# actik-retrofit-r1.net
KiCad netlist of a schematic drawn in EAGLE
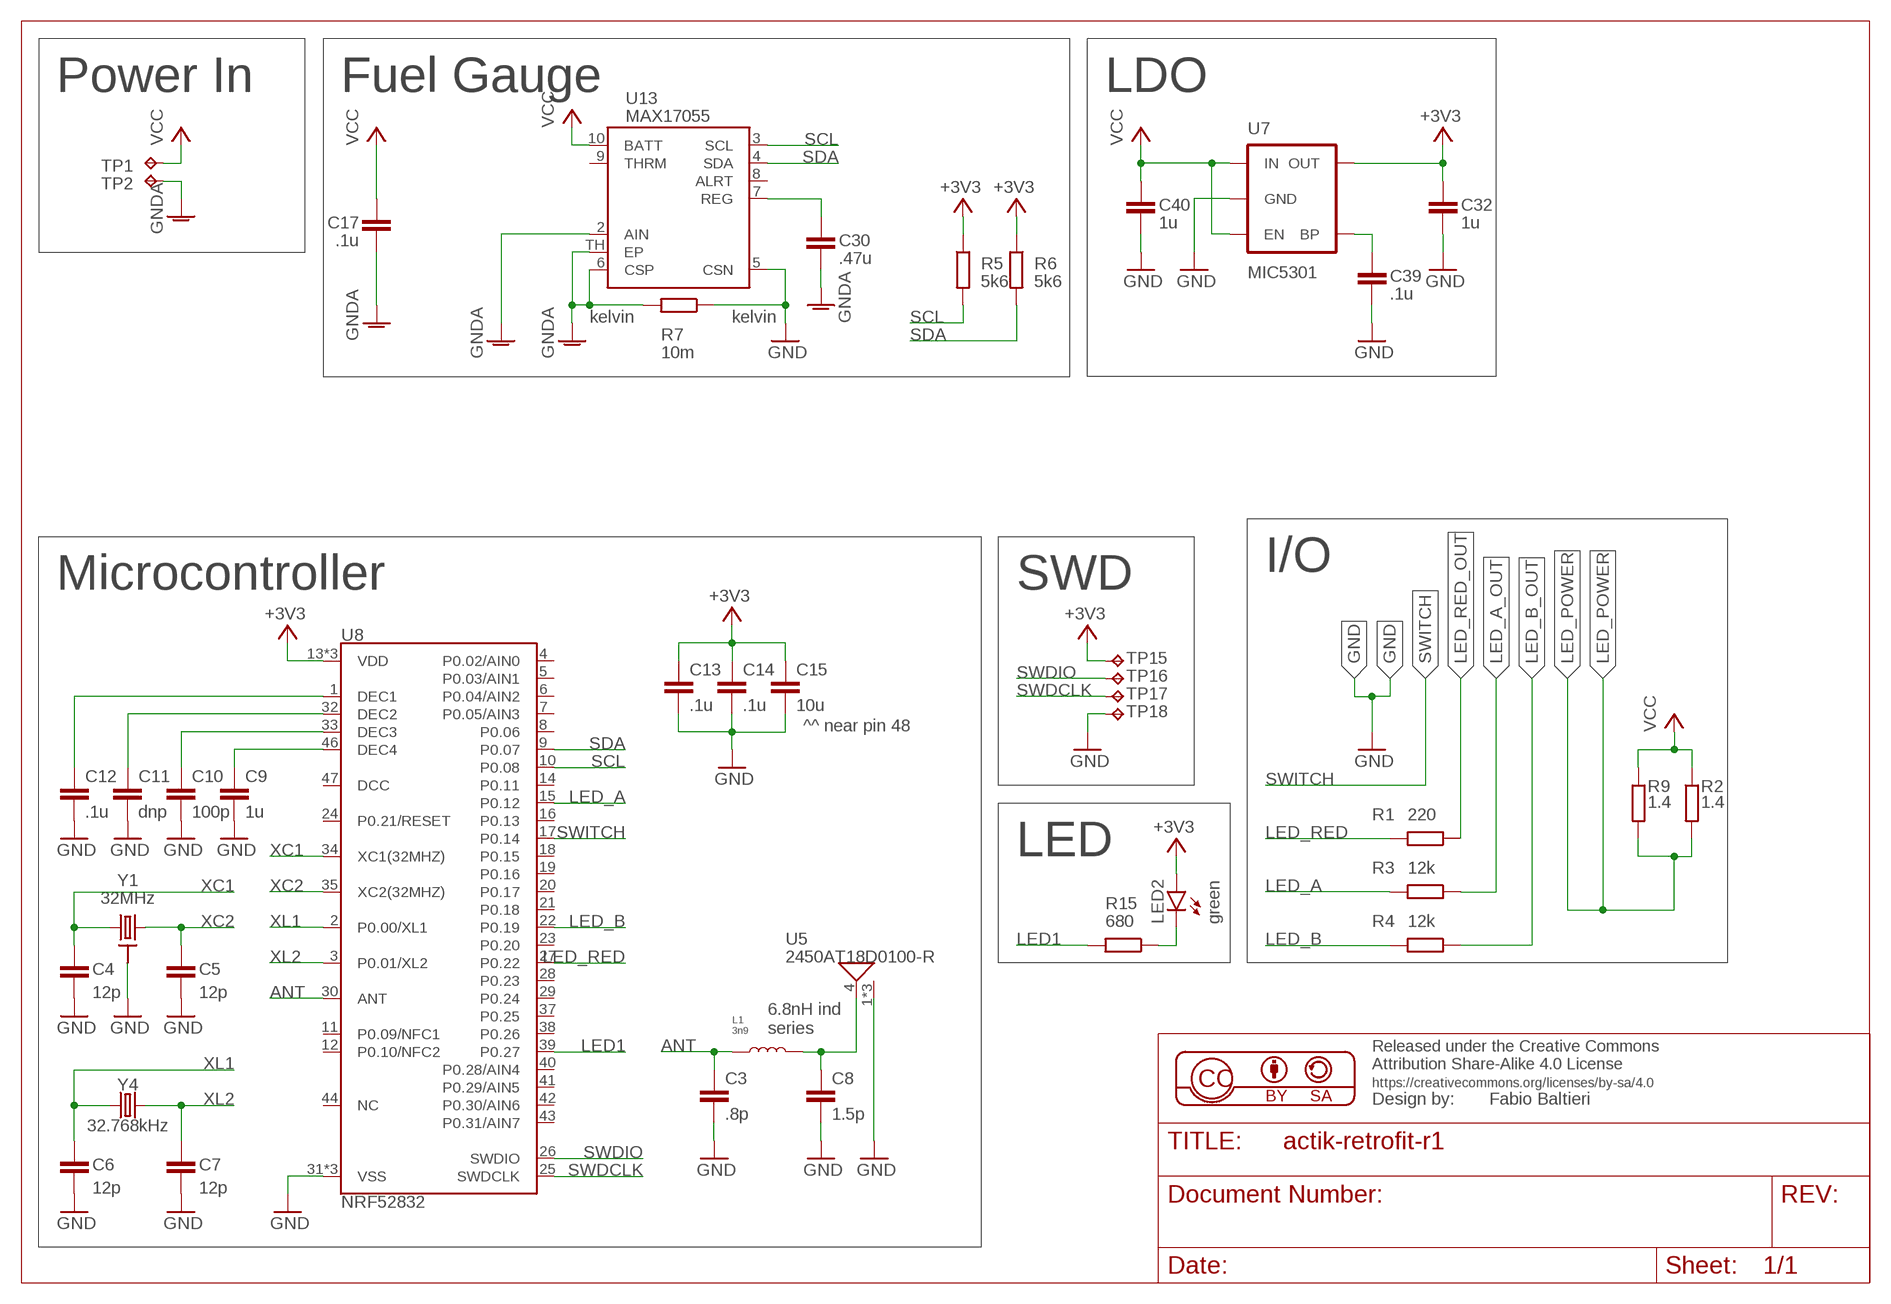
[diagram p0: schematic, sheet 1]

(export (version "E")
  (design (tool "Eeschema 10.0.6"))
  (components
    (comp (ref "C3")
      (value ".8p")
      (footprint "eagle-import:0603")
      (libsource (lib "eagle-import") (part "C0603"))
    )
    (comp (ref "C4")
      (value "12p")
      (footprint "eagle-import:0603")
      (libsource (lib "eagle-import") (part "C0603"))
    )
    (comp (ref "C5")
      (value "12p")
      (footprint "eagle-import:0603")
      (libsource (lib "eagle-import") (part "C0603"))
    )
    (comp (ref "C6")
      (value "12p")
      (footprint "eagle-import:0603")
      (libsource (lib "eagle-import") (part "C0603"))
    )
    (comp (ref "C7")
      (value "12p")
      (footprint "eagle-import:0603")
      (libsource (lib "eagle-import") (part "C0603"))
    )
    (comp (ref "C8")
      (value "1.5p")
      (footprint "eagle-import:0603")
      (libsource (lib "eagle-import") (part "C0603"))
    )
    (comp (ref "C9")
      (value "1u")
      (footprint "eagle-import:0603")
      (libsource (lib "eagle-import") (part "C0603"))
    )
    (comp (ref "C10")
      (value "100p")
      (footprint "eagle-import:0603")
      (libsource (lib "eagle-import") (part "C0603"))
    )
    (comp (ref "C11")
      (value "dnp")
      (footprint "eagle-import:0603")
      (libsource (lib "eagle-import") (part "C0603"))
    )
    (comp (ref "C12")
      (value ".1u")
      (footprint "eagle-import:0603")
      (libsource (lib "eagle-import") (part "C0603"))
    )
    (comp (ref "C13")
      (value ".1u")
      (footprint "eagle-import:0603")
      (libsource (lib "eagle-import") (part "C0603"))
    )
    (comp (ref "C14")
      (value ".1u")
      (footprint "eagle-import:0603")
      (libsource (lib "eagle-import") (part "C0603"))
    )
    (comp (ref "C15")
      (value "10u")
      (footprint "eagle-import:0603")
      (libsource (lib "eagle-import") (part "C0603"))
    )
    (comp (ref "C17")
      (value ".1u")
      (footprint "eagle-import:0603")
      (libsource (lib "eagle-import") (part "C0603"))
    )
    (comp (ref "C30")
      (value ".47u")
      (footprint "eagle-import:0603")
      (libsource (lib "eagle-import") (part "C0603"))
    )
    (comp (ref "C32")
      (value "1u")
      (footprint "eagle-import:0603")
      (libsource (lib "eagle-import") (part "C0603"))
    )
    (comp (ref "C39")
      (value ".1u")
      (footprint "eagle-import:0603")
      (libsource (lib "eagle-import") (part "C0603"))
    )
    (comp (ref "C40")
      (value "1u")
      (footprint "eagle-import:0603")
      (libsource (lib "eagle-import") (part "C0603"))
    )
    (comp (ref "L1")
      (value "3n9")
      (footprint "eagle-import:L0603")
      (libsource (lib "eagle-import") (part "INDUCTOR_0603"))
    )
    (comp (ref "LED2")
      (value "green")
      (footprint "eagle-import:SML0805")
      (libsource (lib "eagle-import") (part "LEDSML0805"))
    )
    (comp (ref "R1")
      (value "220")
      (footprint "eagle-import:0603")
      (libsource (lib "eagle-import") (part "R0603"))
    )
    (comp (ref "R2")
      (value "1.4")
      (footprint "eagle-import:R3225")
      (libsource (lib "eagle-import") (part "R-EU_R3225"))
    )
    (comp (ref "R3")
      (value "12k")
      (footprint "eagle-import:0603")
      (libsource (lib "eagle-import") (part "R0603"))
    )
    (comp (ref "R4")
      (value "12k")
      (footprint "eagle-import:0603")
      (libsource (lib "eagle-import") (part "R0603"))
    )
    (comp (ref "R5")
      (value "5k6")
      (footprint "eagle-import:0603")
      (libsource (lib "eagle-import") (part "R0603"))
    )
    (comp (ref "R6")
      (value "5k6")
      (footprint "eagle-import:0603")
      (libsource (lib "eagle-import") (part "R0603"))
    )
    (comp (ref "R7")
      (value "10m")
      (footprint "eagle-import:0603")
      (libsource (lib "eagle-import") (part "R0603"))
    )
    (comp (ref "R9")
      (value "1.4")
      (footprint "eagle-import:R3225")
      (libsource (lib "eagle-import") (part "R-EU_R3225"))
    )
    (comp (ref "R15")
      (value "680")
      (footprint "eagle-import:0603")
      (libsource (lib "eagle-import") (part "R0603"))
    )
    (comp (ref "TP1")
      (value "TPPAD1-13")
      (footprint "eagle-import:P1-13")
      (libsource (lib "eagle-import") (part "TPPAD1-13"))
    )
    (comp (ref "TP2")
      (value "TPPAD1-13")
      (footprint "eagle-import:P1-13")
      (libsource (lib "eagle-import") (part "TPPAD1-13"))
    )
    (comp (ref "TP15")
      (value "TPTP10R")
      (footprint "eagle-import:TP10R")
      (libsource (lib "eagle-import") (part "TPTP10R"))
    )
    (comp (ref "TP16")
      (value "TPTP10R")
      (footprint "eagle-import:TP10R")
      (libsource (lib "eagle-import") (part "TPTP10R"))
    )
    (comp (ref "TP17")
      (value "TPTP10R")
      (footprint "eagle-import:TP10R")
      (libsource (lib "eagle-import") (part "TPTP10R"))
    )
    (comp (ref "TP18")
      (value "TPTP10R")
      (footprint "eagle-import:TP10R")
      (libsource (lib "eagle-import") (part "TPTP10R"))
    )
    (comp (ref "U5")
      (value "2450AT18D0100-R")
      (footprint "eagle-import:2450AT18D0100-R")
      (libsource (lib "eagle-import") (part "2450AT18D0100-R"))
    )
    (comp (ref "U7")
      (value "MIC5301")
      (footprint "eagle-import:SOT23-5")
      (libsource (lib "eagle-import") (part "V_REG_LDOSMD"))
    )
    (comp (ref "U8")
      (value "NRF52832")
      (footprint "eagle-import:QFN48-6X6MM")
      (libsource (lib "eagle-import") (part "NRF52832"))
    )
    (comp (ref "U13")
      (value "MAX17055")
      (footprint "eagle-import:TDFN10-2X2.5")
      (libsource (lib "eagle-import") (part "MAX17055"))
    )
    (comp (ref "Y1")
      (value "32MHz")
      (footprint "eagle-import:XTAL-2X1.6")
      (libsource (lib "eagle-import") (part "XTAL-GND-2X1.6"))
    )
    (comp (ref "Y4")
      (value "32.768kHz")
      (footprint "eagle-import:CRYSTAL-SMD-3.2X1.5MM")
      (libsource (lib "eagle-import") (part "CRYSTAL-32.768KHZSMD-3.2X1.5"))
    )
  )
  (nets
    (net (code "1") (name "+3V3") (class "Default")
      (node (ref "C13") (pin "1") (pinfunction "1_1") (pintype "passive"))
      (node (ref "C14") (pin "1") (pinfunction "1_1") (pintype "passive"))
      (node (ref "C15") (pin "1") (pinfunction "1_1") (pintype "passive"))
      (node (ref "C32") (pin "1") (pinfunction "1_1") (pintype "passive"))
      (node (ref "LED2") (pin "A") (pinfunction "A_A") (pintype "passive"))
      (node (ref "R5") (pin "1") (pinfunction "1_1") (pintype "passive"))
      (node (ref "R6") (pin "1") (pinfunction "1_1") (pintype "passive"))
      (node (ref "TP15") (pin "TP") (pinfunction "TP_TP") (pintype "input"))
      (node (ref "U7") (pin "5") (pinfunction "OUT_5") (pintype "passive"))
      (node (ref "U8") (pin "13") (pinfunction "VDD_13") (pintype "bidirectional"))
      (node (ref "U8") (pin "36") (pinfunction "VDD_36") (pintype "bidirectional"))
      (node (ref "U8") (pin "48") (pinfunction "VDD_48") (pintype "bidirectional"))
    )
    (net (code "2") (name "/ANT") (class "Default")
      (node (ref "C3") (pin "1") (pinfunction "1_1") (pintype "passive"))
      (node (ref "L1") (pin "P$1") (pinfunction "P$1_P$1") (pintype "passive"))
      (node (ref "U8") (pin "30") (pinfunction "ANT_30") (pintype "bidirectional"))
    )
    (net (code "3") (name "/LED1") (class "Default")
      (node (ref "R15") (pin "2") (pinfunction "2_2") (pintype "passive"))
      (node (ref "U8") (pin "39") (pinfunction "P0.27_39") (pintype "bidirectional"))
    )
    (net (code "4") (name "/LED_A") (class "Default")
      (node (ref "R3") (pin "2") (pinfunction "2_2") (pintype "passive"))
      (node (ref "U8") (pin "15") (pinfunction "P0.12_15") (pintype "bidirectional"))
    )
    (net (code "5") (name "/LED_B") (class "Default")
      (node (ref "R4") (pin "2") (pinfunction "2_2") (pintype "passive"))
      (node (ref "U8") (pin "22") (pinfunction "P0.19_22") (pintype "bidirectional"))
    )
    (net (code "6") (name "/LED_RED") (class "Default")
      (node (ref "R1") (pin "2") (pinfunction "2_2") (pintype "passive"))
      (node (ref "U8") (pin "27") (pinfunction "P0.22_27") (pintype "bidirectional"))
    )
    (net (code "7") (name "/SCL") (class "Default")
      (node (ref "R5") (pin "2") (pinfunction "2_2") (pintype "passive"))
      (node (ref "U13") (pin "3") (pinfunction "SCL_3") (pintype "bidirectional"))
      (node (ref "U8") (pin "10") (pinfunction "P0.08_10") (pintype "bidirectional"))
    )
    (net (code "8") (name "/SDA") (class "Default")
      (node (ref "R6") (pin "2") (pinfunction "2_2") (pintype "passive"))
      (node (ref "U13") (pin "4") (pinfunction "SDA_4") (pintype "bidirectional"))
      (node (ref "U8") (pin "9") (pinfunction "P0.07_9") (pintype "bidirectional"))
    )
    (net (code "9") (name "/SWDCLK") (class "Default")
      (node (ref "TP17") (pin "TP") (pinfunction "TP_TP") (pintype "input"))
      (node (ref "U8") (pin "25") (pinfunction "SWDCLK_25") (pintype "bidirectional"))
    )
    (net (code "10") (name "/SWDIO") (class "Default")
      (node (ref "TP16") (pin "TP") (pinfunction "TP_TP") (pintype "input"))
      (node (ref "U8") (pin "26") (pinfunction "SWDIO_26") (pintype "bidirectional"))
    )
    (net (code "11") (name "/XC1") (class "Default")
      (node (ref "C4") (pin "1") (pinfunction "1_1") (pintype "passive"))
      (node (ref "U8") (pin "34") (pinfunction "XC1(32MHZ)_34") (pintype "bidirectional"))
      (node (ref "Y1") (pin "1") (pinfunction "1_1") (pintype "passive"))
    )
    (net (code "12") (name "/XC2") (class "Default")
      (node (ref "C5") (pin "1") (pinfunction "1_1") (pintype "passive"))
      (node (ref "U8") (pin "35") (pinfunction "XC2(32MHZ)_35") (pintype "bidirectional"))
      (node (ref "Y1") (pin "3") (pinfunction "2_3") (pintype "passive"))
    )
    (net (code "13") (name "/XL1") (class "Default")
      (node (ref "C6") (pin "1") (pinfunction "1_1") (pintype "passive"))
      (node (ref "U8") (pin "2") (pinfunction "P0.00/XL1_2") (pintype "bidirectional"))
      (node (ref "Y4") (pin "P$1") (pinfunction "1_P$1") (pintype "passive"))
    )
    (net (code "14") (name "/XL2") (class "Default")
      (node (ref "C7") (pin "1") (pinfunction "1_1") (pintype "passive"))
      (node (ref "U8") (pin "3") (pinfunction "P0.01/XL2_3") (pintype "bidirectional"))
      (node (ref "Y4") (pin "P$2") (pinfunction "2_P$2") (pintype "passive"))
    )
    (net (code "15") (name "GND") (class "Default")
      (node (ref "C10") (pin "2") (pinfunction "2_2") (pintype "passive"))
      (node (ref "C11") (pin "2") (pinfunction "2_2") (pintype "passive"))
      (node (ref "C12") (pin "2") (pinfunction "2_2") (pintype "passive"))
      (node (ref "C13") (pin "2") (pinfunction "2_2") (pintype "passive"))
      (node (ref "C14") (pin "2") (pinfunction "2_2") (pintype "passive"))
      (node (ref "C15") (pin "2") (pinfunction "2_2") (pintype "passive"))
      (node (ref "C3") (pin "2") (pinfunction "2_2") (pintype "passive"))
      (node (ref "C32") (pin "2") (pinfunction "2_2") (pintype "passive"))
      (node (ref "C39") (pin "2") (pinfunction "2_2") (pintype "passive"))
      (node (ref "C4") (pin "2") (pinfunction "2_2") (pintype "passive"))
      (node (ref "C40") (pin "2") (pinfunction "2_2") (pintype "passive"))
      (node (ref "C5") (pin "2") (pinfunction "2_2") (pintype "passive"))
      (node (ref "C6") (pin "2") (pinfunction "2_2") (pintype "passive"))
      (node (ref "C7") (pin "2") (pinfunction "2_2") (pintype "passive"))
      (node (ref "C8") (pin "2") (pinfunction "2_2") (pintype "passive"))
      (node (ref "C9") (pin "2") (pinfunction "2_2") (pintype "passive"))
      (node (ref "R7") (pin "1") (pinfunction "1_1") (pintype "passive"))
      (node (ref "TP18") (pin "TP") (pinfunction "TP_TP") (pintype "input"))
      (node (ref "U13") (pin "5") (pinfunction "CSN_5") (pintype "bidirectional"))
      (node (ref "U5") (pin "1") (pinfunction "GND_1") (pintype "bidirectional"))
      (node (ref "U5") (pin "2") (pinfunction "GND_2") (pintype "bidirectional"))
      (node (ref "U5") (pin "3") (pinfunction "GND_3") (pintype "bidirectional"))
      (node (ref "U7") (pin "2") (pinfunction "GND_2") (pintype "input"))
      (node (ref "U8") (pin "31") (pinfunction "VSS_31") (pintype "bidirectional"))
      (node (ref "U8") (pin "45") (pinfunction "VSS_45") (pintype "bidirectional"))
      (node (ref "U8") (pin "EP") (pinfunction "VSS_EP") (pintype "bidirectional"))
      (node (ref "Y1") (pin "2") (pinfunction "GND_2") (pintype "passive"))
      (node (ref "Y1") (pin "4") (pinfunction "GND_4") (pintype "passive"))
    )
    (net (code "16") (name "GNDA") (class "Default")
      (node (ref "C17") (pin "2") (pinfunction "2_2") (pintype "passive"))
      (node (ref "C30") (pin "2") (pinfunction "2_2") (pintype "passive"))
      (node (ref "R7") (pin "2") (pinfunction "2_2") (pintype "passive"))
      (node (ref "TP2") (pin "TP") (pinfunction "TP_TP") (pintype "input"))
      (node (ref "U13") (pin "2") (pinfunction "AIN_2") (pintype "bidirectional"))
      (node (ref "U13") (pin "6") (pinfunction "CSP_6") (pintype "bidirectional"))
      (node (ref "U13") (pin "TH") (pinfunction "EP_TH") (pintype "bidirectional"))
    )
    (net (code "17") (name "LED_A_OUT") (class "Default")
      (node (ref "R3") (pin "1") (pinfunction "1_1") (pintype "passive"))
    )
    (net (code "18") (name "LED_B_OUT") (class "Default")
      (node (ref "R4") (pin "1") (pinfunction "1_1") (pintype "passive"))
    )
    (net (code "19") (name "LED_POWER") (class "Default")
      (node (ref "R2") (pin "2") (pinfunction "2_2") (pintype "passive"))
      (node (ref "R9") (pin "2") (pinfunction "2_2") (pintype "passive"))
    )
    (net (code "20") (name "LED_RED_OUT") (class "Default")
      (node (ref "R1") (pin "1") (pinfunction "1_1") (pintype "passive"))
    )
    (net (code "21") (name "Net-(LED2-PadC)") (class "Default")
      (node (ref "LED2") (pin "C") (pinfunction "C_C") (pintype "passive"))
      (node (ref "R15") (pin "1") (pinfunction "1_1") (pintype "passive"))
    )
    (net (code "22") (name "Net-(U5-FEED)") (class "Default")
      (node (ref "C8") (pin "1") (pinfunction "1_1") (pintype "passive"))
      (node (ref "L1") (pin "P$2") (pinfunction "P$2_P$2") (pintype "passive"))
      (node (ref "U5") (pin "4") (pinfunction "FEED_4") (pintype "bidirectional"))
    )
    (net (code "23") (name "Net-(U7-BP)") (class "Default")
      (node (ref "C39") (pin "1") (pinfunction "1_1") (pintype "passive"))
      (node (ref "U7") (pin "4") (pinfunction "BP_4") (pintype "input"))
    )
    (net (code "24") (name "Net-(U8-DEC1)") (class "Default")
      (node (ref "C12") (pin "1") (pinfunction "1_1") (pintype "passive"))
      (node (ref "U8") (pin "1") (pinfunction "DEC1_1") (pintype "bidirectional"))
    )
    (net (code "25") (name "Net-(U8-DEC2)") (class "Default")
      (node (ref "C11") (pin "1") (pinfunction "1_1") (pintype "passive"))
      (node (ref "U8") (pin "32") (pinfunction "DEC2_32") (pintype "bidirectional"))
    )
    (net (code "26") (name "Net-(U8-DEC3)") (class "Default")
      (node (ref "C10") (pin "1") (pinfunction "1_1") (pintype "passive"))
      (node (ref "U8") (pin "33") (pinfunction "DEC3_33") (pintype "bidirectional"))
    )
    (net (code "27") (name "Net-(U8-DEC4)") (class "Default")
      (node (ref "C9") (pin "1") (pinfunction "1_1") (pintype "passive"))
      (node (ref "U8") (pin "46") (pinfunction "DEC4_46") (pintype "bidirectional"))
    )
    (net (code "28") (name "Net-(U13-REG)") (class "Default")
      (node (ref "C30") (pin "1") (pinfunction "1_1") (pintype "passive"))
      (node (ref "U13") (pin "7") (pinfunction "REG_7") (pintype "bidirectional"))
    )
    (net (code "29") (name "SWITCH") (class "Default")
      (node (ref "U8") (pin "17") (pinfunction "P0.14_17") (pintype "bidirectional"))
    )
    (net (code "30") (name "VCC") (class "Default")
      (node (ref "C17") (pin "1") (pinfunction "1_1") (pintype "passive"))
      (node (ref "C40") (pin "1") (pinfunction "1_1") (pintype "passive"))
      (node (ref "R2") (pin "1") (pinfunction "1_1") (pintype "passive"))
      (node (ref "R9") (pin "1") (pinfunction "1_1") (pintype "passive"))
      (node (ref "TP1") (pin "TP") (pinfunction "TP_TP") (pintype "input"))
      (node (ref "U13") (pin "10") (pinfunction "BATT_10") (pintype "bidirectional"))
      (node (ref "U7") (pin "1") (pinfunction "IN_1") (pintype "input"))
      (node (ref "U7") (pin "3") (pinfunction "EN_3") (pintype "input"))
    )
    (net (code "31") (name "unconnected-(U8-DCC-Pad47)") (class "Default")
      (node (ref "U8") (pin "47") (pinfunction "DCC_47") (pintype "bidirectional"))
    )
    (net (code "32") (name "unconnected-(U8-NC-Pad44)") (class "Default")
      (node (ref "U8") (pin "44") (pinfunction "NC_44") (pintype "bidirectional"))
    )
    (net (code "33") (name "unconnected-(U8-P0.02{slash}AIN0-Pad4)") (class "Default")
      (node (ref "U8") (pin "4") (pinfunction "P0.02/AIN0_4") (pintype "bidirectional"))
    )
    (net (code "34") (name "unconnected-(U8-P0.03{slash}AIN1-Pad5)") (class "Default")
      (node (ref "U8") (pin "5") (pinfunction "P0.03/AIN1_5") (pintype "bidirectional"))
    )
    (net (code "35") (name "unconnected-(U8-P0.04{slash}AIN2-Pad6)") (class "Default")
      (node (ref "U8") (pin "6") (pinfunction "P0.04/AIN2_6") (pintype "bidirectional"))
    )
    (net (code "36") (name "unconnected-(U8-P0.05{slash}AIN3-Pad7)") (class "Default")
      (node (ref "U8") (pin "7") (pinfunction "P0.05/AIN3_7") (pintype "bidirectional"))
    )
    (net (code "37") (name "unconnected-(U8-P0.06-Pad8)") (class "Default")
      (node (ref "U8") (pin "8") (pinfunction "P0.06_8") (pintype "bidirectional"))
    )
    (net (code "38") (name "unconnected-(U8-P0.09{slash}NFC1-Pad11)") (class "Default")
      (node (ref "U8") (pin "11") (pinfunction "P0.09/NFC1_11") (pintype "bidirectional"))
    )
    (net (code "39") (name "unconnected-(U8-P0.10{slash}NFC2-Pad12)") (class "Default")
      (node (ref "U8") (pin "12") (pinfunction "P0.10/NFC2_12") (pintype "bidirectional"))
    )
    (net (code "40") (name "unconnected-(U8-P0.11-Pad14)") (class "Default")
      (node (ref "U8") (pin "14") (pinfunction "P0.11_14") (pintype "bidirectional"))
    )
    (net (code "41") (name "unconnected-(U8-P0.13-Pad16)") (class "Default")
      (node (ref "U8") (pin "16") (pinfunction "P0.13_16") (pintype "bidirectional"))
    )
    (net (code "42") (name "unconnected-(U8-P0.15-Pad18)") (class "Default")
      (node (ref "U8") (pin "18") (pinfunction "P0.15_18") (pintype "bidirectional"))
    )
    (net (code "43") (name "unconnected-(U8-P0.16-Pad19)") (class "Default")
      (node (ref "U8") (pin "19") (pinfunction "P0.16_19") (pintype "bidirectional"))
    )
    (net (code "44") (name "unconnected-(U8-P0.17-Pad20)") (class "Default")
      (node (ref "U8") (pin "20") (pinfunction "P0.17_20") (pintype "bidirectional"))
    )
    (net (code "45") (name "unconnected-(U8-P0.18-Pad21)") (class "Default")
      (node (ref "U8") (pin "21") (pinfunction "P0.18_21") (pintype "bidirectional"))
    )
    (net (code "46") (name "unconnected-(U8-P0.20-Pad23)") (class "Default")
      (node (ref "U8") (pin "23") (pinfunction "P0.20_23") (pintype "bidirectional"))
    )
    (net (code "47") (name "unconnected-(U8-P0.21{slash}RESET-Pad24)") (class "Default")
      (node (ref "U8") (pin "24") (pinfunction "P0.21/RESET_24") (pintype "bidirectional"))
    )
    (net (code "48") (name "unconnected-(U8-P0.23-Pad28)") (class "Default")
      (node (ref "U8") (pin "28") (pinfunction "P0.23_28") (pintype "bidirectional"))
    )
    (net (code "49") (name "unconnected-(U8-P0.24-Pad29)") (class "Default")
      (node (ref "U8") (pin "29") (pinfunction "P0.24_29") (pintype "bidirectional"))
    )
    (net (code "50") (name "unconnected-(U8-P0.25-Pad37)") (class "Default")
      (node (ref "U8") (pin "37") (pinfunction "P0.25_37") (pintype "bidirectional"))
    )
    (net (code "51") (name "unconnected-(U8-P0.26-Pad38)") (class "Default")
      (node (ref "U8") (pin "38") (pinfunction "P0.26_38") (pintype "bidirectional"))
    )
    (net (code "52") (name "unconnected-(U8-P0.28{slash}AIN4-Pad40)") (class "Default")
      (node (ref "U8") (pin "40") (pinfunction "P0.28/AIN4_40") (pintype "bidirectional"))
    )
    (net (code "53") (name "unconnected-(U8-P0.29{slash}AIN5-Pad41)") (class "Default")
      (node (ref "U8") (pin "41") (pinfunction "P0.29/AIN5_41") (pintype "bidirectional"))
    )
    (net (code "54") (name "unconnected-(U8-P0.30{slash}AIN6-Pad42)") (class "Default")
      (node (ref "U8") (pin "42") (pinfunction "P0.30/AIN6_42") (pintype "bidirectional"))
    )
    (net (code "55") (name "unconnected-(U8-P0.31{slash}AIN7-Pad43)") (class "Default")
      (node (ref "U8") (pin "43") (pinfunction "P0.31/AIN7_43") (pintype "bidirectional"))
    )
    (net (code "56") (name "unconnected-(U13-ALRT-Pad8)") (class "Default")
      (node (ref "U13") (pin "8") (pinfunction "ALRT_8") (pintype "bidirectional"))
    )
    (net (code "57") (name "unconnected-(U13-THRM-Pad9)") (class "Default")
      (node (ref "U13") (pin "9") (pinfunction "THRM_9") (pintype "bidirectional"))
    )
  )
)
